# Driver_Ampli.net
KiCad netlist of a schematic drawn in Altium Designer
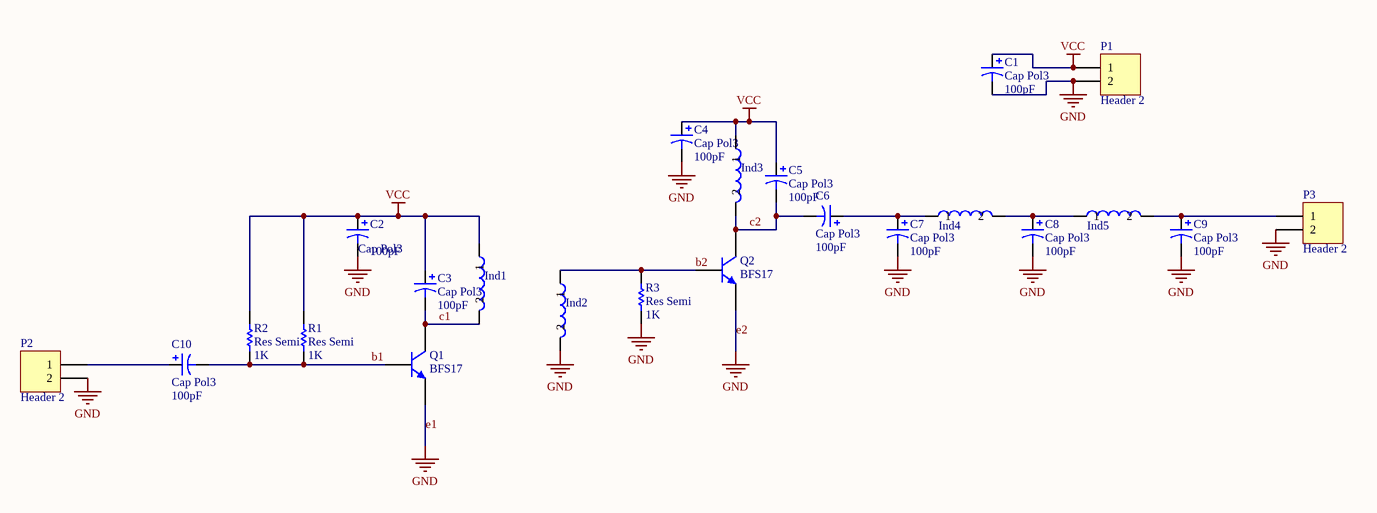
[diagram p0: Driver_Ampli.SchDoc]

(export (version "E")
  (design (tool "Eeschema 10.0.6"))
  (components
    (comp (ref "C1")
      (value "Cap Pol3")
      (footprint "C0805")
      (description "Polarized Capacitor (Surface Mount)")
      (fields (field (name "ALTIUM_VALUE") "100pF") (field (name "PUBLISHER") "Altium Limited"))
      (libsource (lib "Miscellaneous Devices") (part "Cap Pol3"))
    )
    (comp (ref "C2")
      (value "Cap Pol3")
      (footprint "C0805")
      (description "Polarized Capacitor (Surface Mount)")
      (fields (field (name "ALTIUM_VALUE") "100pF") (field (name "PUBLISHER") "Altium Limited"))
      (libsource (lib "Miscellaneous Devices") (part "Cap Pol3"))
    )
    (comp (ref "C3")
      (value "Cap Pol3")
      (footprint "C0805")
      (description "Polarized Capacitor (Surface Mount)")
      (fields (field (name "ALTIUM_VALUE") "100pF") (field (name "PUBLISHER") "Altium Limited"))
      (libsource (lib "Miscellaneous Devices") (part "Cap Pol3"))
    )
    (comp (ref "C4")
      (value "Cap Pol3")
      (footprint "C0805")
      (description "Polarized Capacitor (Surface Mount)")
      (fields (field (name "ALTIUM_VALUE") "100pF") (field (name "PUBLISHER") "Altium Limited"))
      (libsource (lib "Miscellaneous Devices") (part "Cap Pol3"))
    )
    (comp (ref "C5")
      (value "Cap Pol3")
      (footprint "C0805")
      (description "Polarized Capacitor (Surface Mount)")
      (fields (field (name "ALTIUM_VALUE") "100pF") (field (name "PUBLISHER") "Altium Limited"))
      (libsource (lib "Miscellaneous Devices") (part "Cap Pol3"))
    )
    (comp (ref "C6")
      (value "Cap Pol3")
      (footprint "C0805")
      (description "Polarized Capacitor (Surface Mount)")
      (fields (field (name "ALTIUM_VALUE") "100pF") (field (name "PUBLISHER") "Altium Limited"))
      (libsource (lib "Miscellaneous Devices") (part "Cap Pol3"))
    )
    (comp (ref "C7")
      (value "Cap Pol3")
      (footprint "C0805")
      (description "Polarized Capacitor (Surface Mount)")
      (fields (field (name "ALTIUM_VALUE") "100pF") (field (name "PUBLISHER") "Altium Limited"))
      (libsource (lib "Miscellaneous Devices") (part "Cap Pol3"))
    )
    (comp (ref "C8")
      (value "Cap Pol3")
      (footprint "C0805")
      (description "Polarized Capacitor (Surface Mount)")
      (fields (field (name "ALTIUM_VALUE") "100pF") (field (name "PUBLISHER") "Altium Limited"))
      (libsource (lib "Miscellaneous Devices") (part "Cap Pol3"))
    )
    (comp (ref "C9")
      (value "Cap Pol3")
      (footprint "C0805")
      (description "Polarized Capacitor (Surface Mount)")
      (fields (field (name "ALTIUM_VALUE") "100pF") (field (name "PUBLISHER") "Altium Limited"))
      (libsource (lib "Miscellaneous Devices") (part "Cap Pol3"))
    )
    (comp (ref "C10")
      (value "Cap Pol3")
      (footprint "C0805")
      (description "Polarized Capacitor (Surface Mount)")
      (fields (field (name "ALTIUM_VALUE") "100pF") (field (name "PUBLISHER") "Altium Limited"))
      (libsource (lib "Miscellaneous Devices") (part "Cap Pol3"))
    )
    (comp (ref "Ind1") (value "Ind2") (footprint "Ind_3mm") (libsource (lib "epf") (part "Ind2")))
    (comp (ref "Ind2") (value "Ind2") (footprint "Ind_3mm") (libsource (lib "epf") (part "Ind2")))
    (comp (ref "Ind3") (value "Ind2") (footprint "Ind_3mm") (libsource (lib "epf") (part "Ind2")))
    (comp (ref "Ind4") (value "Ind2") (footprint "Ind_3mm") (libsource (lib "epf") (part "Ind2")))
    (comp (ref "Ind5") (value "Ind2") (footprint "Ind_3mm") (libsource (lib "epf") (part "Ind2")))
    (comp (ref "P1")
      (value "Header 2")
      (footprint "HDR1X2")
      (description "Header, 2-Pin")
      (fields (field (name "PUBLISHER") "Altium Limited"))
      (libsource (lib "Miscellaneous Connectors") (part "Header 2"))
    )
    (comp (ref "P2")
      (value "Header 2")
      (footprint "HDR1X2")
      (description "Header, 2-Pin")
      (fields (field (name "PUBLISHER") "Altium Limited"))
      (libsource (lib "") (part "Header 2_1"))
    )
    (comp (ref "P3")
      (value "Header 2")
      (footprint "HDR1X2")
      (description "Header, 2-Pin")
      (fields (field (name "PUBLISHER") "Altium Limited"))
      (libsource (lib "Miscellaneous Connectors") (part "Header 2"))
    )
    (comp (ref "Q1")
      (value "BFS17")
      (footprint "SOT23")
      (description "NPN 1 GHz Wideband Transistor")
      (fields (field (name "PUBLISHER") "Altium Limited"))
      (libsource (lib "Philips Discrete BJT - RF Transistor") (part "BFS17"))
    )
    (comp (ref "Q2")
      (value "BFS17")
      (footprint "SOT23")
      (description "NPN 1 GHz Wideband Transistor")
      (fields (field (name "PUBLISHER") "Altium Limited"))
      (libsource (lib "Philips Discrete BJT - RF Transistor") (part "BFS17"))
    )
    (comp (ref "R1")
      (value "Res Semi")
      (footprint "2012[0805]")
      (description "Semiconductor Resistor")
      (fields (field (name "ALTIUM_VALUE") "1K") (field (name "PUBLISHER") "Altium Limited"))
      (libsource (lib "Miscellaneous Devices") (part "Res Semi"))
    )
    (comp (ref "R2")
      (value "Res Semi")
      (footprint "2012[0805]")
      (description "Semiconductor Resistor")
      (fields (field (name "ALTIUM_VALUE") "1K") (field (name "PUBLISHER") "Altium Limited"))
      (libsource (lib "Miscellaneous Devices") (part "Res Semi"))
    )
    (comp (ref "R3")
      (value "Res Semi")
      (footprint "2012[0805]")
      (description "Semiconductor Resistor")
      (fields (field (name "ALTIUM_VALUE") "1K") (field (name "PUBLISHER") "Altium Limited"))
      (libsource (lib "Miscellaneous Devices") (part "Res Semi"))
    )
  )
  (nets
    (net (code "1") (name "/b1") (class "Default")
      (node (ref "C10") (pin "2") (pinfunction "2_2") (pintype "passive"))
      (node (ref "Q1") (pin "1") (pinfunction "B_1") (pintype "passive"))
      (node (ref "R1") (pin "1") (pinfunction "1_1") (pintype "passive"))
      (node (ref "R2") (pin "1") (pinfunction "1_1") (pintype "passive"))
    )
    (net (code "2") (name "/b2") (class "Default")
      (node (ref "Ind2") (pin "1") (pinfunction "1_1") (pintype "passive"))
      (node (ref "Q2") (pin "1") (pinfunction "B_1") (pintype "passive"))
      (node (ref "R3") (pin "2") (pinfunction "2_2") (pintype "passive"))
    )
    (net (code "3") (name "/c1") (class "Default")
      (node (ref "C3") (pin "2") (pinfunction "2_2") (pintype "passive"))
      (node (ref "Ind1") (pin "2") (pinfunction "2_2") (pintype "passive"))
      (node (ref "Q1") (pin "3") (pinfunction "C_3") (pintype "passive"))
    )
    (net (code "4") (name "/c2") (class "Default")
      (node (ref "C5") (pin "2") (pinfunction "2_2") (pintype "passive"))
      (node (ref "C6") (pin "2") (pinfunction "2_2") (pintype "passive"))
      (node (ref "Ind3") (pin "2") (pinfunction "2_2") (pintype "passive"))
      (node (ref "Q2") (pin "3") (pinfunction "C_3") (pintype "passive"))
    )
    (net (code "5") (name "GND") (class "Default")
      (node (ref "C1") (pin "2") (pinfunction "2_2") (pintype "passive"))
      (node (ref "C2") (pin "2") (pinfunction "2_2") (pintype "passive"))
      (node (ref "C4") (pin "2") (pinfunction "2_2") (pintype "passive"))
      (node (ref "C7") (pin "2") (pinfunction "2_2") (pintype "passive"))
      (node (ref "C8") (pin "2") (pinfunction "2_2") (pintype "passive"))
      (node (ref "C9") (pin "2") (pinfunction "2_2") (pintype "passive"))
      (node (ref "Ind2") (pin "2") (pinfunction "2_2") (pintype "passive"))
      (node (ref "P1") (pin "2") (pinfunction "2_2") (pintype "passive"))
      (node (ref "P2") (pin "2") (pinfunction "2_2") (pintype "passive"))
      (node (ref "P3") (pin "2") (pinfunction "2_2") (pintype "passive"))
      (node (ref "Q1") (pin "2") (pinfunction "E_2") (pintype "passive"))
      (node (ref "Q2") (pin "2") (pinfunction "E_2") (pintype "passive"))
      (node (ref "R3") (pin "1") (pinfunction "1_1") (pintype "passive"))
    )
    (net (code "6") (name "Net-(C6-Pad1)") (class "Default")
      (node (ref "C6") (pin "1") (pinfunction "1_1") (pintype "passive"))
      (node (ref "C7") (pin "1") (pinfunction "1_1") (pintype "passive"))
      (node (ref "Ind4") (pin "1") (pinfunction "1_1") (pintype "passive"))
    )
    (net (code "7") (name "Net-(C8-Pad1)") (class "Default")
      (node (ref "C8") (pin "1") (pinfunction "1_1") (pintype "passive"))
      (node (ref "Ind4") (pin "2") (pinfunction "2_2") (pintype "passive"))
      (node (ref "Ind5") (pin "1") (pinfunction "1_1") (pintype "passive"))
    )
    (net (code "8") (name "Net-(C9-Pad1)") (class "Default")
      (node (ref "C9") (pin "1") (pinfunction "1_1") (pintype "passive"))
      (node (ref "Ind5") (pin "2") (pinfunction "2_2") (pintype "passive"))
      (node (ref "P3") (pin "1") (pinfunction "1_1") (pintype "passive"))
    )
    (net (code "9") (name "Net-(C10-Pad1)") (class "Default")
      (node (ref "C10") (pin "1") (pinfunction "1_1") (pintype "passive"))
      (node (ref "P2") (pin "1") (pinfunction "1_1") (pintype "passive"))
    )
    (net (code "10") (name "VCC") (class "Default")
      (node (ref "C1") (pin "1") (pinfunction "1_1") (pintype "passive"))
      (node (ref "C2") (pin "1") (pinfunction "1_1") (pintype "passive"))
      (node (ref "C3") (pin "1") (pinfunction "1_1") (pintype "passive"))
      (node (ref "C4") (pin "1") (pinfunction "1_1") (pintype "passive"))
      (node (ref "C5") (pin "1") (pinfunction "1_1") (pintype "passive"))
      (node (ref "Ind1") (pin "1") (pinfunction "1_1") (pintype "passive"))
      (node (ref "Ind3") (pin "1") (pinfunction "1_1") (pintype "passive"))
      (node (ref "P1") (pin "1") (pinfunction "1_1") (pintype "passive"))
      (node (ref "R1") (pin "2") (pinfunction "2_2") (pintype "passive"))
      (node (ref "R2") (pin "2") (pinfunction "2_2") (pintype "passive"))
    )
  )
)
